# Power_supply_-_Copy.net
KiCad netlist of a schematic drawn in Altium Designer
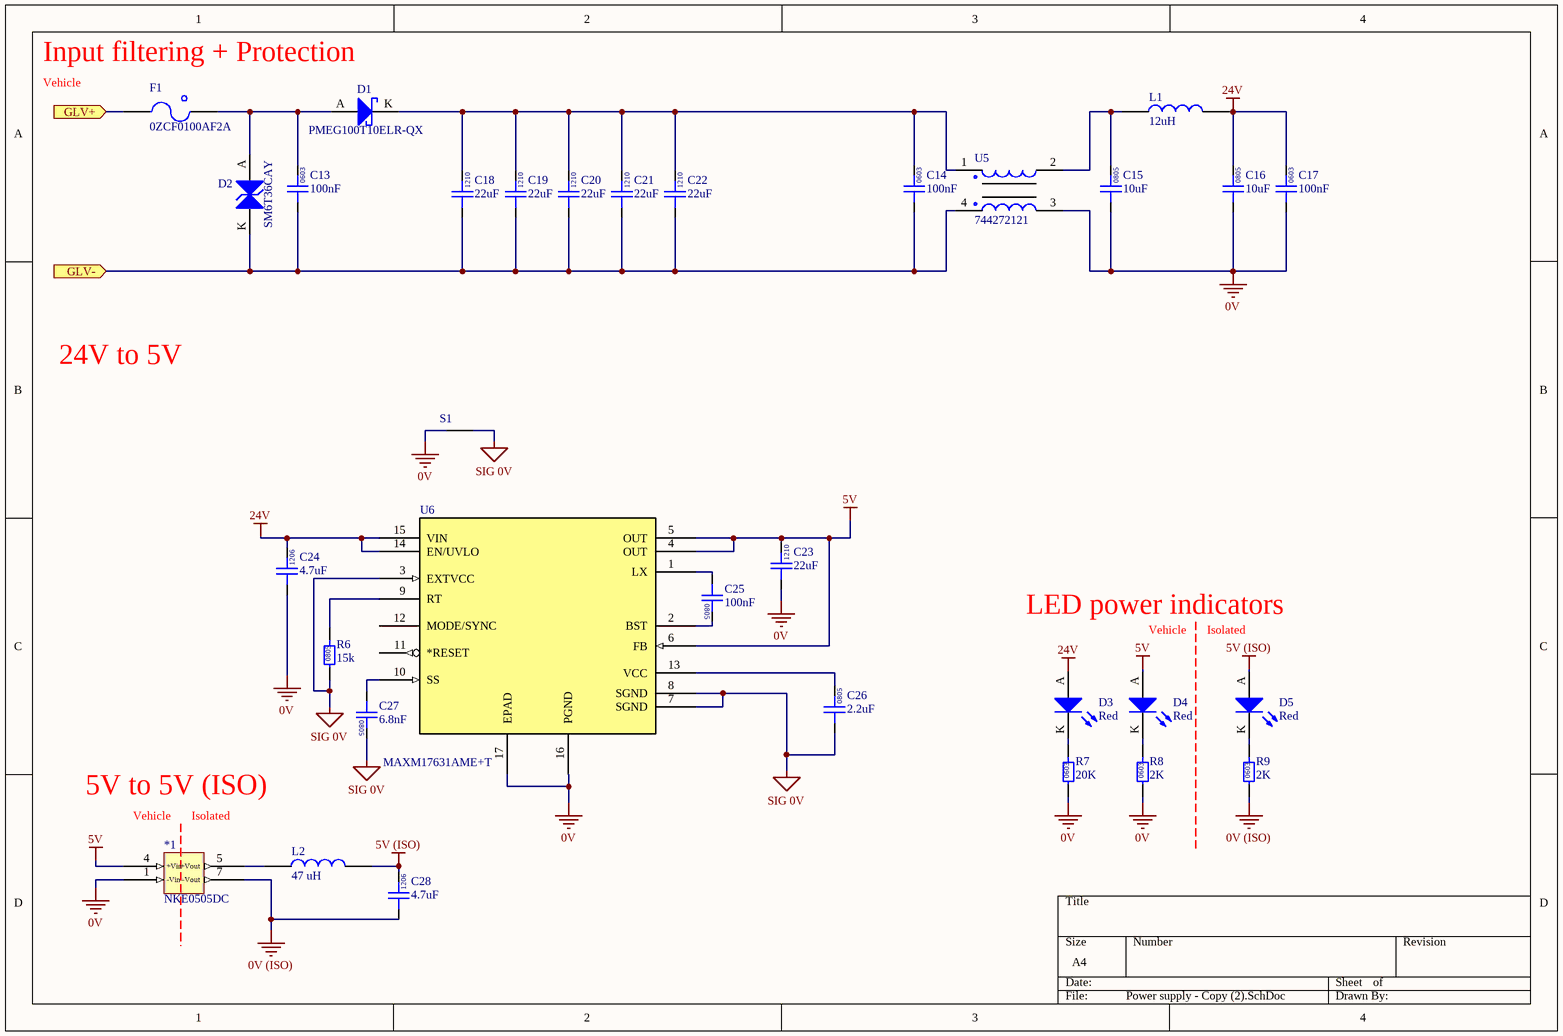
[diagram p0: Power supply - Copy (2).SchDoc]

(export (version "E")
  (design (tool "Eeschema 10.0.6"))
  (components
    (comp (ref "*1")
      (value "NKE0505DC")
      (footprint "NKE0505DC")
      (description "DC DC CONVERTER 5V 1W")
      (fields
        (field (name "MANUFACTURER") "Murata Power Solutions Inc.")
        (field (name "DIGIKEY PART NUMBER") "811-1433-5-ND")
      )
      (libsource (lib "ts_standard_library") (part "NKE0505DC"))
    )
    (comp (ref "C13")
      (value "100nF")
      (footprint "0603")
      (fields
        (field (name "PART NUMBER") "GCM188L81H104KA57D")
        (field (name "MANUFACTURER") "muRata")
        (field (name "TOLERANCE") "±10%")
      )
      (libsource (lib "ts_standard_library") (part "Capacitor 0603"))
    )
    (comp (ref "C14")
      (value "100nF")
      (footprint "0603")
      (fields
        (field (name "PART NUMBER") "GCM188L81H104KA57D")
        (field (name "MANUFACTURER") "muRata")
        (field (name "TOLERANCE") "±10%")
      )
      (libsource (lib "ts_standard_library") (part "Capacitor 0603"))
    )
    (comp (ref "C15")
      (value "10uF")
      (footprint "0805")
      (fields
        (field (name "PART NUMBER") "GRM21BR6YA106KE43L")
        (field (name "MANUFACTURER") "muRata")
        (field (name "TOLERANCE") "10%")
      )
      (libsource (lib "ts_standard_library") (part "Capacitor 0805"))
    )
    (comp (ref "C16")
      (value "10uF")
      (footprint "0805")
      (fields
        (field (name "PART NUMBER") "GRM21BR6YA106KE43L")
        (field (name "MANUFACTURER") "muRata")
        (field (name "TOLERANCE") "10%")
      )
      (libsource (lib "ts_standard_library") (part "Capacitor 0805"))
    )
    (comp (ref "C17")
      (value "100nF")
      (footprint "0603")
      (fields
        (field (name "PART NUMBER") "GCM188L81H104KA57D")
        (field (name "MANUFACTURER") "muRata")
        (field (name "TOLERANCE") "±10%")
      )
      (libsource (lib "ts_standard_library") (part "Capacitor 0603"))
    )
    (comp (ref "C18")
      (value "22uF")
      (footprint "1210")
      (fields
        (field (name "PART NUMBER") "GRM32ER71E226KE15L")
        (field (name "MANUFACTURER") "Murata Electronics")
        (field (name "TOLERANCE") "±10%")
      )
      (libsource (lib "ts_standard_library") (part "Capacitor 1210"))
    )
    (comp (ref "C19")
      (value "22uF")
      (footprint "1210")
      (fields
        (field (name "PART NUMBER") "GRM32ER71E226KE15L")
        (field (name "MANUFACTURER") "Murata Electronics")
        (field (name "TOLERANCE") "±10%")
      )
      (libsource (lib "ts_standard_library") (part "Capacitor 1210"))
    )
    (comp (ref "C20")
      (value "22uF")
      (footprint "1210")
      (fields
        (field (name "PART NUMBER") "GRM32ER71E226KE15L")
        (field (name "MANUFACTURER") "Murata Electronics")
        (field (name "TOLERANCE") "±10%")
      )
      (libsource (lib "ts_standard_library") (part "Capacitor 1210"))
    )
    (comp (ref "C21")
      (value "22uF")
      (footprint "1210")
      (fields
        (field (name "PART NUMBER") "GRM32ER71E226KE15L")
        (field (name "MANUFACTURER") "Murata Electronics")
        (field (name "TOLERANCE") "±10%")
      )
      (libsource (lib "ts_standard_library") (part "Capacitor 1210"))
    )
    (comp (ref "C22")
      (value "22uF")
      (footprint "1210")
      (fields
        (field (name "PART NUMBER") "GRM32ER71E226KE15L")
        (field (name "MANUFACTURER") "Murata Electronics")
        (field (name "TOLERANCE") "±10%")
      )
      (libsource (lib "ts_standard_library") (part "Capacitor 1210"))
    )
    (comp (ref "C23")
      (value "22uF")
      (footprint "1210")
      (fields
        (field (name "PART NUMBER") "GRM32ER71E226KE15L")
        (field (name "MANUFACTURER") "Murata Electronics")
        (field (name "TOLERANCE") "±10%")
      )
      (libsource (lib "ts_standard_library") (part "Capacitor 1210"))
    )
    (comp (ref "C24")
      (value "4.7uF")
      (footprint "1206 CAP")
      (fields
        (field (name "PART NUMBER") "GRM31CR71H475KA12K")
        (field (name "MANUFACTURER") "Murata Electronics")
        (field (name "TOLERANCE") "±10%")
      )
      (libsource (lib "ts_standard_library") (part "Capacitor 1206"))
    )
    (comp (ref "C25")
      (value "100nF")
      (footprint "0805")
      (fields
        (field (name "PART NUMBER") "GCM21BR71H104KA37L")
        (field (name "MANUFACTURER") "muRata")
        (field (name "TOLERANCE") "±10%")
      )
      (libsource (lib "ts_standard_library") (part "Capacitor 0805"))
    )
    (comp (ref "C26")
      (value "2.2uF")
      (footprint "0805")
      (fields
        (field (name "PART NUMBER") "GRM21BR71E225KE11L")
        (field (name "MANUFACTURER") "Murata Electronics")
        (field (name "TOLERANCE") "±10%")
      )
      (libsource (lib "ts_standard_library") (part "Capacitor 0805"))
    )
    (comp (ref "C27")
      (value "6.8nF")
      (footprint "0805")
      (fields
        (field (name "PART NUMBER") "GCM2195C1H682JA16D")
        (field (name "MANUFACTURER") "muRata")
        (field (name "TOLERANCE") "±5%")
      )
      (libsource (lib "ts_standard_library") (part "Capacitor 0805"))
    )
    (comp (ref "C28")
      (value "4.7uF")
      (footprint "1206 CAP")
      (fields
        (field (name "PART NUMBER") "GRM31CR71H475KA12K")
        (field (name "MANUFACTURER") "Murata Electronics")
        (field (name "TOLERANCE") "±10%")
      )
      (libsource (lib "ts_standard_library") (part "Capacitor 1206"))
    )
    (comp (ref "D1")
      (value "PMEG100T10ELR-QX")
      (footprint "NXP SOD123W")
      (fields
        (field (name "MANUFACTURER") "Nexperia USA Inc.")
        (field (name "DIGIKEY PART NUMBER") "1727-PMEG100T10ELR-QXCT-ND")
      )
      (libsource (lib "ts_standard_library") (part "Diode (Schottky)"))
    )
    (comp (ref "D2")
      (value "SM6T36CAY")
      (footprint "ST SMB DIODE")
      (fields
        (field (name "MANUFACTURER") "STMicroelectronics")
        (field (name "DIGIKEY PART NUMBER") "497-10804-1-ND")
      )
      (libsource (lib "ts_standard_library") (part "TVS (Bidirectional)"))
    )
    (comp (ref "D3")
      (value "Red")
      (footprint "0805 LED")
      (description "Red LED Indication - Discrete 1.75V 0805 (2012 Metric)")
      (fields (field (name "PART NUMBER") "SML-210LTT86") (field (name "MANUFACTURER") "ROHM Semiconductor"))
      (libsource (lib "ts_standard_library") (part "LED"))
    )
    (comp (ref "D4")
      (value "Red")
      (footprint "0805 LED")
      (description "Red LED Indication - Discrete 1.75V 0805 (2012 Metric)")
      (fields (field (name "PART NUMBER") "SML-210LTT86") (field (name "MANUFACTURER") "ROHM Semiconductor"))
      (libsource (lib "ts_standard_library") (part "LED"))
    )
    (comp (ref "D5")
      (value "Red")
      (footprint "0805 LED")
      (description "Red LED Indication - Discrete 1.75V 0805 (2012 Metric)")
      (fields (field (name "PART NUMBER") "SML-210LTT86") (field (name "MANUFACTURER") "ROHM Semiconductor"))
      (libsource (lib "ts_standard_library") (part "LED"))
    )
    (comp (ref "F1")
      (value "0ZCF0100AF2A")
      (footprint "2920")
      (description "PTC RESET FUSE 60V 1A 292")
      (fields
        (field (name "MANUFACTURER") "Littelfuse Inc.")
        (field (name "DIGIKEY PART NUMBER") "507-2070-1-ND")
      )
      (libsource (lib "ts_standard_library") (part "PTC Fuse"))
    )
    (comp (ref "L1")
      (value "12uH")
      (footprint "1812")
      (fields
        (field (name "PART NUMBER") "RLS-126")
        (field (name "MANUFACTURER") "Recom")
        (field (name "TOLERANCE") "0.2")
      )
      (libsource (lib "ts_standard_library") (part "Inductor"))
    )
    (comp (ref "L2")
      (value "47 uH")
      (footprint "82473C")
      (fields
        (field (name "PART NUMBER") "82473C")
        (field (name "MANUFACTURER") "Murata Power Solutions Inc.")
        (field (name "TOLERANCE") "0.1")
      )
      (libsource (lib "ts_standard_library") (part "Inductor"))
    )
    (comp (ref "R6")
      (value "15k")
      (footprint "0805")
      (fields
        (field (name "PART NUMBER") "RC0805FR0715KL")
        (field (name "MANUFACTURER") "YAGEO")
        (field (name "TOLERANCE") "0.01")
      )
      (libsource (lib "ts_standard_library") (part "Resistor 0805"))
    )
    (comp (ref "R7")
      (value "20K")
      (footprint "0603")
      (fields
        (field (name "PART NUMBER") "RC0603FR-0720KL")
        (field (name "MANUFACTURER") "YAGEO")
        (field (name "TOLERANCE") "0.01")
      )
      (libsource (lib "ts_standard_library") (part "Resistor 0603"))
    )
    (comp (ref "R8")
      (value "2K")
      (footprint "0603")
      (fields
        (field (name "PART NUMBER") "RC0603FR-072KL")
        (field (name "MANUFACTURER") "YAGEO")
        (field (name "TOLERANCE") "0.01")
      )
      (libsource (lib "ts_standard_library") (part "Resistor 0603"))
    )
    (comp (ref "R9")
      (value "2K")
      (footprint "0603")
      (fields
        (field (name "PART NUMBER") "RC0603FR-072KL")
        (field (name "MANUFACTURER") "YAGEO")
        (field (name "TOLERANCE") "0.01")
      )
      (libsource (lib "ts_standard_library") (part "Resistor 0603"))
    )
    (comp (ref "S1")
      (value "~")
      (footprint "POINT_0_1")
      (fields (field (name "PART NUMBER") "STAR_POINT_0.1"))
      (libsource (lib "ts_standard_library") (part "Star"))
    )
    (comp (ref "U5")
      (value "744272121")
      (footprint "Wurth 4-PC Pad")
      (fields
        (field (name "MANUFACTURER") "Wurth Electronics Inc")
        (field (name "DIGIKEY PART NUMBER") "732-1489-1-ND")
      )
      (libsource (lib "ts_standard_library") (part "CM Choke"))
    )
    (comp (ref "U6")
      (value "MAXM17631AME+T")
      (footprint "MAXM17631AME+T")
      (description "DC DC CONVERTER 5V")
      (fields
        (field (name "MANUFACTURER") "Analog Devices")
        (field (name "DIGIKEY PART NUMBER") "175-MAXM17631AME+TTR-ND")
      )
      (libsource (lib "ts_standard_library") (part "MAXM17631AME+T"))
    )
  )
  (nets
    (net (code "1") (name "/GLV+") (class "Default")
      (node (ref "F1") (pin "1") (pinfunction "1_1") (pintype "passive"))
    )
    (net (code "2") (name "/GLV-") (class "Default")
      (node (ref "C13") (pin "1") (pinfunction "1_1") (pintype "passive"))
      (node (ref "C14") (pin "1") (pinfunction "1_1") (pintype "passive"))
      (node (ref "C18") (pin "1") (pinfunction "1_1") (pintype "passive"))
      (node (ref "C19") (pin "1") (pinfunction "1_1") (pintype "passive"))
      (node (ref "C20") (pin "1") (pinfunction "1_1") (pintype "passive"))
      (node (ref "C21") (pin "1") (pinfunction "1_1") (pintype "passive"))
      (node (ref "C22") (pin "1") (pinfunction "1_1") (pintype "passive"))
      (node (ref "D2") (pin "K") (pinfunction "K_K") (pintype "passive"))
      (node (ref "U5") (pin "4") (pinfunction "4_4") (pintype "passive"))
    )
    (net (code "3") (name "0V") (class "Default")
      (node (ref "*1") (pin "1") (pinfunction "-Vin_1") (pintype "input"))
      (node (ref "C15") (pin "1") (pinfunction "1_1") (pintype "passive"))
      (node (ref "C16") (pin "1") (pinfunction "1_1") (pintype "passive"))
      (node (ref "C17") (pin "1") (pinfunction "1_1") (pintype "passive"))
      (node (ref "C23") (pin "1") (pinfunction "1_1") (pintype "passive"))
      (node (ref "C24") (pin "1") (pinfunction "1_1") (pintype "passive"))
      (node (ref "R7") (pin "1") (pinfunction "1_1") (pintype "passive"))
      (node (ref "R8") (pin "1") (pinfunction "1_1") (pintype "passive"))
      (node (ref "S1") (pin "1") (pinfunction "1_1") (pintype "passive"))
      (node (ref "U5") (pin "3") (pinfunction "3_3") (pintype "power_in"))
      (node (ref "U6") (pin "16") (pinfunction "PGND_16") (pintype "power_in"))
      (node (ref "U6") (pin "17") (pinfunction "EPAD_17") (pintype "power_in"))
    )
    (net (code "4") (name "0V (ISO)") (class "Default")
      (node (ref "*1") (pin "7") (pinfunction "-Vout_7") (pintype "output"))
      (node (ref "C28") (pin "1") (pinfunction "1_1") (pintype "passive"))
      (node (ref "R9") (pin "1") (pinfunction "1_1") (pintype "passive"))
    )
    (net (code "5") (name "5V") (class "Default")
      (node (ref "*1") (pin "4") (pinfunction "+Vin_4") (pintype "input"))
      (node (ref "C23") (pin "2") (pinfunction "2_2") (pintype "passive"))
      (node (ref "D4") (pin "A") (pinfunction "A_A") (pintype "passive"))
      (node (ref "U6") (pin "4") (pinfunction "OUT_4") (pintype "power_in"))
      (node (ref "U6") (pin "5") (pinfunction "OUT_5") (pintype "power_in"))
      (node (ref "U6") (pin "6") (pinfunction "FB_6") (pintype "input"))
    )
    (net (code "6") (name "5V (ISO)") (class "Default")
      (node (ref "C28") (pin "2") (pinfunction "2_2") (pintype "passive"))
      (node (ref "D5") (pin "A") (pinfunction "A_A") (pintype "passive"))
      (node (ref "L2") (pin "1") (pinfunction "1_1") (pintype "passive"))
    )
    (net (code "7") (name "24V") (class "Default")
      (node (ref "C16") (pin "2") (pinfunction "2_2") (pintype "passive"))
      (node (ref "C17") (pin "2") (pinfunction "2_2") (pintype "passive"))
      (node (ref "C24") (pin "2") (pinfunction "2_2") (pintype "passive"))
      (node (ref "D3") (pin "A") (pinfunction "A_A") (pintype "passive"))
      (node (ref "L1") (pin "1") (pinfunction "1_1") (pintype "passive"))
      (node (ref "U6") (pin "14") (pinfunction "EN/UVLO_14") (pintype "passive"))
      (node (ref "U6") (pin "15") (pinfunction "VIN_15") (pintype "power_in"))
    )
    (net (code "8") (name "Net-(*1-+Vout)") (class "Default")
      (node (ref "*1") (pin "5") (pinfunction "+Vout_5") (pintype "output"))
      (node (ref "L2") (pin "2") (pinfunction "2_2") (pintype "passive"))
    )
    (net (code "9") (name "Net-(C13-Pad2)") (class "Default")
      (node (ref "C13") (pin "2") (pinfunction "2_2") (pintype "passive"))
      (node (ref "D1") (pin "A") (pinfunction "A_A") (pintype "passive"))
      (node (ref "D2") (pin "A") (pinfunction "A_A") (pintype "passive"))
      (node (ref "F1") (pin "2") (pinfunction "2_2") (pintype "passive"))
    )
    (net (code "10") (name "Net-(C14-Pad2)") (class "Default")
      (node (ref "C14") (pin "2") (pinfunction "2_2") (pintype "passive"))
      (node (ref "C18") (pin "2") (pinfunction "2_2") (pintype "passive"))
      (node (ref "C19") (pin "2") (pinfunction "2_2") (pintype "passive"))
      (node (ref "C20") (pin "2") (pinfunction "2_2") (pintype "passive"))
      (node (ref "C21") (pin "2") (pinfunction "2_2") (pintype "passive"))
      (node (ref "C22") (pin "2") (pinfunction "2_2") (pintype "passive"))
      (node (ref "D1") (pin "K") (pinfunction "K_K") (pintype "passive"))
      (node (ref "U5") (pin "1") (pinfunction "1_1") (pintype "passive"))
    )
    (net (code "11") (name "Net-(C15-Pad2)") (class "Default")
      (node (ref "C15") (pin "2") (pinfunction "2_2") (pintype "passive"))
      (node (ref "L1") (pin "2") (pinfunction "2_2") (pintype "passive"))
      (node (ref "U5") (pin "2") (pinfunction "2_2") (pintype "passive"))
    )
    (net (code "12") (name "Net-(D3-PadK)") (class "Default")
      (node (ref "D3") (pin "K") (pinfunction "K_K") (pintype "passive"))
      (node (ref "R7") (pin "2") (pinfunction "2_2") (pintype "passive"))
    )
    (net (code "13") (name "Net-(D4-PadK)") (class "Default")
      (node (ref "D4") (pin "K") (pinfunction "K_K") (pintype "passive"))
      (node (ref "R8") (pin "2") (pinfunction "2_2") (pintype "passive"))
    )
    (net (code "14") (name "Net-(D5-PadK)") (class "Default")
      (node (ref "D5") (pin "K") (pinfunction "K_K") (pintype "passive"))
      (node (ref "R9") (pin "2") (pinfunction "2_2") (pintype "passive"))
    )
    (net (code "15") (name "Net-(U6-BST)") (class "Default")
      (node (ref "C25") (pin "2") (pinfunction "2_2") (pintype "passive"))
      (node (ref "U6") (pin "2") (pinfunction "BST_2") (pintype "passive"))
    )
    (net (code "16") (name "Net-(U6-LX)") (class "Default")
      (node (ref "C25") (pin "1") (pinfunction "1_1") (pintype "passive"))
      (node (ref "U6") (pin "1") (pinfunction "LX_1") (pintype "passive"))
    )
    (net (code "17") (name "Net-(U6-RT)") (class "Default")
      (node (ref "R6") (pin "2") (pinfunction "2_2") (pintype "passive"))
      (node (ref "U6") (pin "9") (pinfunction "RT_9") (pintype "passive"))
    )
    (net (code "18") (name "Net-(U6-SS)") (class "Default")
      (node (ref "C27") (pin "1") (pinfunction "1_1") (pintype "passive"))
      (node (ref "U6") (pin "10") (pinfunction "SS_10") (pintype "input"))
    )
    (net (code "19") (name "Net-(U6-VCC)") (class "Default")
      (node (ref "C26") (pin "2") (pinfunction "2_2") (pintype "passive"))
      (node (ref "U6") (pin "13") (pinfunction "VCC_13") (pintype "power_in"))
    )
    (net (code "20") (name "SIG 0V") (class "Default")
      (node (ref "C26") (pin "1") (pinfunction "1_1") (pintype "passive"))
      (node (ref "C27") (pin "2") (pinfunction "2_2") (pintype "passive"))
      (node (ref "R6") (pin "1") (pinfunction "1_1") (pintype "passive"))
      (node (ref "S1") (pin "2") (pinfunction "2_2") (pintype "passive"))
      (node (ref "U6") (pin "3") (pinfunction "EXTVCC_3") (pintype "input"))
      (node (ref "U6") (pin "7") (pinfunction "SGND_7") (pintype "power_in"))
      (node (ref "U6") (pin "8") (pinfunction "SGND_8") (pintype "power_in"))
    )
    (net (code "21") (name "unconnected-(U6-*RESET-Pad11)") (class "Default")
      (node (ref "U6") (pin "11") (pinfunction "*RESET_11") (pintype "output"))
    )
    (net (code "22") (name "unconnected-(U6-MODE{slash}SYNC-Pad12)") (class "Default")
      (node (ref "U6") (pin "12") (pinfunction "MODE/SYNC_12") (pintype "passive"))
    )
  )
)
